# design.net
KiCad netlist of a schematic drawn in Altium Designer
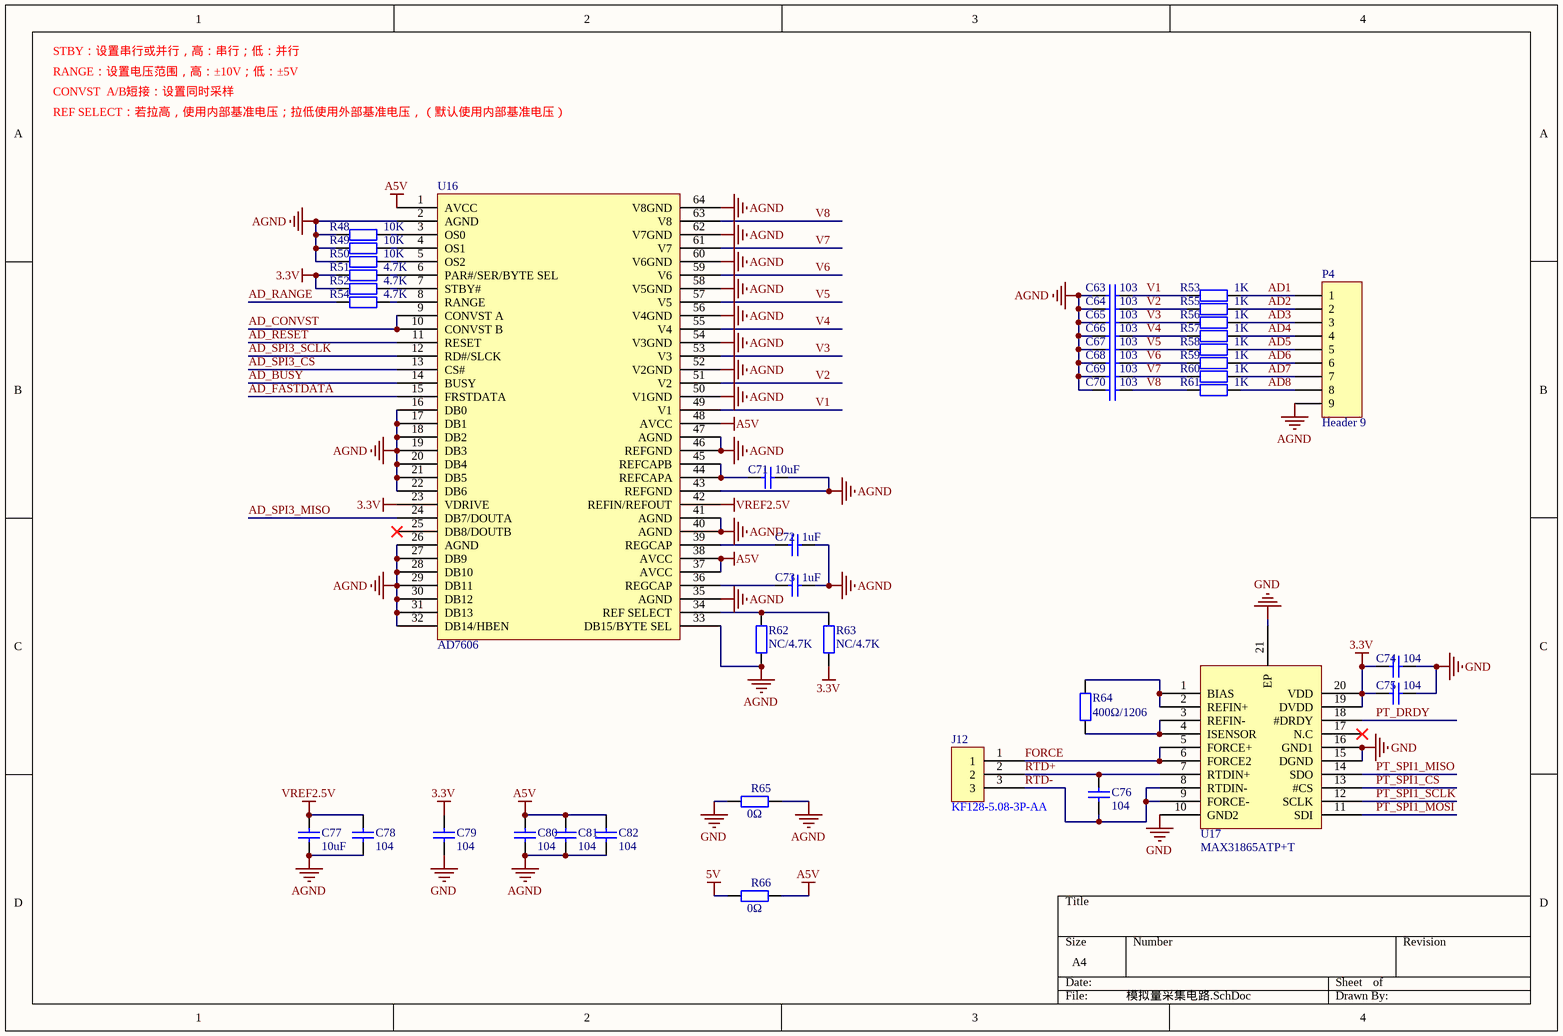
[diagram p0: 模拟量采集电路.SchDoc]

(export (version "E")
  (design (tool "Eeschema 10.0.6"))
  (components
    (comp (ref "C63")
      (value "103")
      (footprint "C 0603_L")
      (description "0603贴片电容")
      (fields (field (name "PUBLISHER") "Altium Limited"))
      (libsource (lib "STM32_PLC_20251215") (part "Cap"))
    )
    (comp (ref "C64")
      (value "103")
      (footprint "C 0603_L")
      (description "0603贴片电容")
      (fields (field (name "PUBLISHER") "Altium Limited"))
      (libsource (lib "STM32_PLC_20251215") (part "Cap"))
    )
    (comp (ref "C65")
      (value "103")
      (footprint "C 0603_L")
      (description "0603贴片电容")
      (fields (field (name "PUBLISHER") "Altium Limited"))
      (libsource (lib "STM32_PLC_20251215") (part "Cap"))
    )
    (comp (ref "C66")
      (value "103")
      (footprint "C 0603_L")
      (description "0603贴片电容")
      (fields (field (name "PUBLISHER") "Altium Limited"))
      (libsource (lib "STM32_PLC_20251215") (part "Cap"))
    )
    (comp (ref "C67")
      (value "103")
      (footprint "C 0603_L")
      (description "0603贴片电容")
      (fields (field (name "PUBLISHER") "Altium Limited"))
      (libsource (lib "STM32_PLC_20251215") (part "Cap"))
    )
    (comp (ref "C68")
      (value "103")
      (footprint "C 0603_L")
      (description "0603贴片电容")
      (fields (field (name "PUBLISHER") "Altium Limited"))
      (libsource (lib "STM32_PLC_20251215") (part "Cap"))
    )
    (comp (ref "C69")
      (value "103")
      (footprint "C 0603_L")
      (description "0603贴片电容")
      (fields (field (name "PUBLISHER") "Altium Limited"))
      (libsource (lib "STM32_PLC_20251215") (part "Cap"))
    )
    (comp (ref "C70")
      (value "103")
      (footprint "C 0603_L")
      (description "0603贴片电容")
      (fields (field (name "PUBLISHER") "Altium Limited"))
      (libsource (lib "STM32_PLC_20251215") (part "Cap"))
    )
    (comp (ref "C71")
      (value "10uF")
      (footprint "C 0603_L")
      (description "0603贴片电容")
      (fields (field (name "PUBLISHER") "Altium Limited"))
      (libsource (lib "STM32_PLC_20251215") (part "Cap"))
    )
    (comp (ref "C72")
      (value "1uF")
      (footprint "C 0603_L")
      (description "0603贴片电容")
      (fields (field (name "PUBLISHER") "Altium Limited"))
      (libsource (lib "STM32_PLC_20251215") (part "Cap"))
    )
    (comp (ref "C73")
      (value "1uF")
      (footprint "C 0603_L")
      (description "0603贴片电容")
      (fields (field (name "PUBLISHER") "Altium Limited"))
      (libsource (lib "STM32_PLC_20251215") (part "Cap"))
    )
    (comp (ref "C74")
      (value "104")
      (footprint "C 0603_L")
      (description "0603贴片电容")
      (fields (field (name "PUBLISHER") "Altium Limited"))
      (libsource (lib "STM32_PLC_20251215") (part "Cap"))
    )
    (comp (ref "C75")
      (value "104")
      (footprint "C 0603_L")
      (description "0603贴片电容")
      (fields (field (name "PUBLISHER") "Altium Limited"))
      (libsource (lib "STM32_PLC_20251215") (part "Cap"))
    )
    (comp (ref "C76")
      (value "104")
      (footprint "C 0603_L")
      (description "0603贴片电容")
      (fields (field (name "PUBLISHER") "Altium Limited"))
      (libsource (lib "STM32_PLC_20251215") (part "Cap"))
    )
    (comp (ref "C77")
      (value "10uF")
      (footprint "C 0603_L")
      (description "0603贴片电容")
      (fields (field (name "PUBLISHER") "Altium Limited"))
      (libsource (lib "STM32_PLC_20251215") (part "Cap"))
    )
    (comp (ref "C78")
      (value "104")
      (footprint "C 0603_L")
      (description "0603贴片电容")
      (fields (field (name "PUBLISHER") "Altium Limited"))
      (libsource (lib "STM32_PLC_20251215") (part "Cap"))
    )
    (comp (ref "C79")
      (value "104")
      (footprint "C 0603_L")
      (description "0603贴片电容")
      (fields (field (name "PUBLISHER") "Altium Limited"))
      (libsource (lib "STM32_PLC_20251215") (part "Cap"))
    )
    (comp (ref "C80")
      (value "104")
      (footprint "C 0603_L")
      (description "0603贴片电容")
      (fields (field (name "PUBLISHER") "Altium Limited"))
      (libsource (lib "STM32_PLC_20251215") (part "Cap"))
    )
    (comp (ref "C81")
      (value "104")
      (footprint "C 0603_L")
      (description "0603贴片电容")
      (fields (field (name "PUBLISHER") "Altium Limited"))
      (libsource (lib "STM32_PLC_20251215") (part "Cap"))
    )
    (comp (ref "C82")
      (value "104")
      (footprint "C 0603_L")
      (description "0603贴片电容")
      (fields (field (name "PUBLISHER") "Altium Limited"))
      (libsource (lib "STM32_PLC_20251215") (part "Cap"))
    )
    (comp (ref "J12")
      (value "KF128-5.08-3P-AA")
      (footprint "KF128-5.08-3P")
      (description "KF128-5.08-3P-AA端座")
      (fields (field (name "MANUFACTURER") "KEFA(科发)"))
      (libsource (lib "STM32_PLC_20251215") (part "KF128-5.08-3P-AA"))
    )
    (comp (ref "P4")
      (value "Header 9")
      (footprint "KF128-5.08-9P")
      (description "Header, 9-Pin")
      (fields (field (name "PUBLISHER") "Altium Limited"))
      (libsource (lib "Miscellaneous Connectors") (part "Header 9"))
    )
    (comp (ref "R48")
      (value "10K")
      (footprint "R 0603_L")
      (description "0603贴片电阻")
      (fields (field (name "版权归属") "源创客"))
      (libsource (lib "STM32_PLC_20251215") (part "Res"))
    )
    (comp (ref "R49")
      (value "10K")
      (footprint "R 0603_L")
      (description "0603贴片电阻")
      (fields (field (name "版权归属") "源创客"))
      (libsource (lib "STM32_PLC_20251215") (part "Res"))
    )
    (comp (ref "R50")
      (value "10K")
      (footprint "R 0603_L")
      (description "0603贴片电阻")
      (fields (field (name "版权归属") "源创客"))
      (libsource (lib "STM32_PLC_20251215") (part "Res"))
    )
    (comp (ref "R51")
      (value "4.7K")
      (footprint "R 0603_L")
      (description "0603贴片电阻")
      (fields (field (name "版权归属") "源创客"))
      (libsource (lib "STM32_PLC_20251215") (part "Res"))
    )
    (comp (ref "R52")
      (value "4.7K")
      (footprint "R 0603_L")
      (description "0603贴片电阻")
      (fields (field (name "版权归属") "源创客"))
      (libsource (lib "STM32_PLC_20251215") (part "Res"))
    )
    (comp (ref "R53")
      (value "1K")
      (footprint "R 0603_L")
      (description "0603贴片电阻")
      (fields (field (name "版权归属") "源创客"))
      (libsource (lib "STM32_PLC_20251215") (part "Res"))
    )
    (comp (ref "R54")
      (value "4.7K")
      (footprint "R 0603_L")
      (description "0603贴片电阻")
      (fields (field (name "版权归属") "源创客"))
      (libsource (lib "STM32_PLC_20251215") (part "Res"))
    )
    (comp (ref "R55")
      (value "1K")
      (footprint "R 0603_L")
      (description "0603贴片电阻")
      (fields (field (name "版权归属") "源创客"))
      (libsource (lib "STM32_PLC_20251215") (part "Res"))
    )
    (comp (ref "R56")
      (value "1K")
      (footprint "R 0603_L")
      (description "0603贴片电阻")
      (fields (field (name "版权归属") "源创客"))
      (libsource (lib "STM32_PLC_20251215") (part "Res"))
    )
    (comp (ref "R57")
      (value "1K")
      (footprint "R 0603_L")
      (description "0603贴片电阻")
      (fields (field (name "版权归属") "源创客"))
      (libsource (lib "STM32_PLC_20251215") (part "Res"))
    )
    (comp (ref "R58")
      (value "1K")
      (footprint "R 0603_L")
      (description "0603贴片电阻")
      (fields (field (name "版权归属") "源创客"))
      (libsource (lib "STM32_PLC_20251215") (part "Res"))
    )
    (comp (ref "R59")
      (value "1K")
      (footprint "R 0603_L")
      (description "0603贴片电阻")
      (fields (field (name "版权归属") "源创客"))
      (libsource (lib "STM32_PLC_20251215") (part "Res"))
    )
    (comp (ref "R60")
      (value "1K")
      (footprint "R 0603_L")
      (description "0603贴片电阻")
      (fields (field (name "版权归属") "源创客"))
      (libsource (lib "STM32_PLC_20251215") (part "Res"))
    )
    (comp (ref "R61")
      (value "1K")
      (footprint "R 0603_L")
      (description "0603贴片电阻")
      (fields (field (name "版权归属") "源创客"))
      (libsource (lib "STM32_PLC_20251215") (part "Res"))
    )
    (comp (ref "R62")
      (value "NC/4.7K")
      (footprint "R 0603_L")
      (description "0603贴片电阻")
      (fields (field (name "版权归属") "源创客"))
      (libsource (lib "STM32_PLC_20251215") (part "Res"))
    )
    (comp (ref "R63")
      (value "NC/4.7K")
      (footprint "R 0603_L")
      (description "0603贴片电阻")
      (fields (field (name "版权归属") "源创客"))
      (libsource (lib "STM32_PLC_20251215") (part "Res"))
    )
    (comp (ref "R64")
      (value "400Ω/1206")
      (footprint "R1206_L")
      (description "0603贴片电阻")
      (fields (field (name "版权归属") "源创客"))
      (libsource (lib "STM32_PLC_20251215") (part "Res"))
    )
    (comp (ref "R65")
      (value "0Ω")
      (footprint "R 0603_L")
      (description "0603贴片电阻")
      (fields (field (name "版权归属") "源创客"))
      (libsource (lib "STM32_PLC_20251215") (part "Res"))
    )
    (comp (ref "R66")
      (value "0Ω")
      (footprint "R 0603_L")
      (description "0603贴片电阻")
      (fields (field (name "版权归属") "源创客"))
      (libsource (lib "STM32_PLC_20251215") (part "Res"))
    )
    (comp (ref "U16")
      (value "AD7606")
      (footprint "LQFP64 10x10_M")
      (libsource (lib "STM32F407_PLC_20260104_") (part "AD7606"))
    )
    (comp (ref "U17")
      (value "MAX31865ATP+T")
      (footprint "QFN-20_L5.0-W5.0-P0.65-BL-EP")
      (fields (field (name "MANUFACTURER") "ADI(亚德诺)/MAXIM(美信)"))
      (libsource (lib "STM32F407_PLC_20260104_") (part "MAX31865ATP+T"))
    )
  )
  (nets
    (net (code "1") (name "/AD1") (class "Default")
      (node (ref "P4") (pin "1") (pinfunction "1_1") (pintype "passive"))
      (node (ref "R53") (pin "1") (pinfunction "1_1") (pintype "passive"))
    )
    (net (code "2") (name "/AD2") (class "Default")
      (node (ref "P4") (pin "2") (pinfunction "2_2") (pintype "passive"))
      (node (ref "R55") (pin "1") (pinfunction "1_1") (pintype "passive"))
    )
    (net (code "3") (name "/AD3") (class "Default")
      (node (ref "P4") (pin "3") (pinfunction "3_3") (pintype "passive"))
      (node (ref "R56") (pin "1") (pinfunction "1_1") (pintype "passive"))
    )
    (net (code "4") (name "/AD4") (class "Default")
      (node (ref "P4") (pin "4") (pinfunction "4_4") (pintype "passive"))
      (node (ref "R57") (pin "1") (pinfunction "1_1") (pintype "passive"))
    )
    (net (code "5") (name "/AD5") (class "Default")
      (node (ref "P4") (pin "5") (pinfunction "5_5") (pintype "passive"))
      (node (ref "R58") (pin "1") (pinfunction "1_1") (pintype "passive"))
    )
    (net (code "6") (name "/AD6") (class "Default")
      (node (ref "P4") (pin "6") (pinfunction "6_6") (pintype "passive"))
      (node (ref "R59") (pin "1") (pinfunction "1_1") (pintype "passive"))
    )
    (net (code "7") (name "/AD7") (class "Default")
      (node (ref "P4") (pin "7") (pinfunction "7_7") (pintype "passive"))
      (node (ref "R60") (pin "1") (pinfunction "1_1") (pintype "passive"))
    )
    (net (code "8") (name "/AD8") (class "Default")
      (node (ref "P4") (pin "8") (pinfunction "8_8") (pintype "passive"))
      (node (ref "R61") (pin "1") (pinfunction "1_1") (pintype "passive"))
    )
    (net (code "9") (name "/AD_BUSY") (class "Default")
      (node (ref "U16") (pin "14") (pinfunction "BUSY_14") (pintype "passive"))
    )
    (net (code "10") (name "/AD_CONVST") (class "Default")
      (node (ref "U16") (pin "10") (pinfunction "CONVST_B_10") (pintype "passive"))
      (node (ref "U16") (pin "9") (pinfunction "CONVST_A_9") (pintype "passive"))
    )
    (net (code "11") (name "/AD_FASTDATA") (class "Default")
      (node (ref "U16") (pin "15") (pinfunction "FRSTDATA_15") (pintype "passive"))
    )
    (net (code "12") (name "/AD_RANGE") (class "Default")
      (node (ref "R54") (pin "2") (pinfunction "2_2") (pintype "passive"))
    )
    (net (code "13") (name "/AD_RESET") (class "Default")
      (node (ref "U16") (pin "11") (pinfunction "RESET_11") (pintype "passive"))
    )
    (net (code "14") (name "/AD_SPI3_CS") (class "Default")
      (node (ref "U16") (pin "13") (pinfunction "CS#_13") (pintype "passive"))
    )
    (net (code "15") (name "/AD_SPI3_MISO") (class "Default")
      (node (ref "U16") (pin "24") (pinfunction "DB7/DOUTA_24") (pintype "passive"))
    )
    (net (code "16") (name "/AD_SPI3_SCLK") (class "Default")
      (node (ref "U16") (pin "12") (pinfunction "RD#/SLCK_12") (pintype "passive"))
    )
    (net (code "17") (name "/FORCE") (class "Default")
      (node (ref "J12") (pin "1") (pinfunction "1_1") (pintype "passive"))
      (node (ref "U17") (pin "5") (pinfunction "FORCE+_5") (pintype "passive"))
      (node (ref "U17") (pin "6") (pinfunction "FORCE2_6") (pintype "passive"))
    )
    (net (code "18") (name "/PT_DRDY") (class "Default")
      (node (ref "U17") (pin "18") (pinfunction "#DRDY_18") (pintype "passive"))
    )
    (net (code "19") (name "/PT_SPI1_CS") (class "Default")
      (node (ref "U17") (pin "13") (pinfunction "#CS_13") (pintype "passive"))
    )
    (net (code "20") (name "/PT_SPI1_MISO") (class "Default")
      (node (ref "U17") (pin "14") (pinfunction "SDO_14") (pintype "passive"))
    )
    (net (code "21") (name "/PT_SPI1_MOSI") (class "Default")
      (node (ref "U17") (pin "11") (pinfunction "SDI_11") (pintype "passive"))
    )
    (net (code "22") (name "/PT_SPI1_SCLK") (class "Default")
      (node (ref "U17") (pin "12") (pinfunction "SCLK_12") (pintype "passive"))
    )
    (net (code "23") (name "/RTD+") (class "Default")
      (node (ref "C76") (pin "2") (pinfunction "2_2") (pintype "passive"))
      (node (ref "J12") (pin "2") (pinfunction "2_2") (pintype "passive"))
      (node (ref "U17") (pin "7") (pinfunction "RTDIN+_7") (pintype "passive"))
    )
    (net (code "24") (name "/RTD-") (class "Default")
      (node (ref "C76") (pin "1") (pinfunction "1_1") (pintype "passive"))
      (node (ref "J12") (pin "3") (pinfunction "3_3") (pintype "passive"))
      (node (ref "U17") (pin "8") (pinfunction "RTDIN-_8") (pintype "passive"))
      (node (ref "U17") (pin "9") (pinfunction "FORCE-_9") (pintype "passive"))
    )
    (net (code "25") (name "/V1") (class "Default")
      (node (ref "C63") (pin "1") (pinfunction "1_1") (pintype "passive"))
      (node (ref "R53") (pin "2") (pinfunction "2_2") (pintype "passive"))
      (node (ref "U16") (pin "49") (pinfunction "V1_49") (pintype "passive"))
    )
    (net (code "26") (name "/V2") (class "Default")
      (node (ref "C64") (pin "1") (pinfunction "1_1") (pintype "passive"))
      (node (ref "R55") (pin "2") (pinfunction "2_2") (pintype "passive"))
      (node (ref "U16") (pin "51") (pinfunction "V2_51") (pintype "passive"))
    )
    (net (code "27") (name "/V3") (class "Default")
      (node (ref "C65") (pin "1") (pinfunction "1_1") (pintype "passive"))
      (node (ref "R56") (pin "2") (pinfunction "2_2") (pintype "passive"))
      (node (ref "U16") (pin "53") (pinfunction "V3_53") (pintype "passive"))
    )
    (net (code "28") (name "/V4") (class "Default")
      (node (ref "C66") (pin "1") (pinfunction "1_1") (pintype "passive"))
      (node (ref "R57") (pin "2") (pinfunction "2_2") (pintype "passive"))
      (node (ref "U16") (pin "55") (pinfunction "V4_55") (pintype "passive"))
    )
    (net (code "29") (name "/V5") (class "Default")
      (node (ref "C67") (pin "1") (pinfunction "1_1") (pintype "passive"))
      (node (ref "R58") (pin "2") (pinfunction "2_2") (pintype "passive"))
      (node (ref "U16") (pin "57") (pinfunction "V5_57") (pintype "passive"))
    )
    (net (code "30") (name "/V6") (class "Default")
      (node (ref "C68") (pin "1") (pinfunction "1_1") (pintype "passive"))
      (node (ref "R59") (pin "2") (pinfunction "2_2") (pintype "passive"))
      (node (ref "U16") (pin "59") (pinfunction "V6_59") (pintype "passive"))
    )
    (net (code "31") (name "/V7") (class "Default")
      (node (ref "C69") (pin "1") (pinfunction "1_1") (pintype "passive"))
      (node (ref "R60") (pin "2") (pinfunction "2_2") (pintype "passive"))
      (node (ref "U16") (pin "61") (pinfunction "V7_61") (pintype "passive"))
    )
    (net (code "32") (name "/V8") (class "Default")
      (node (ref "C70") (pin "1") (pinfunction "1_1") (pintype "passive"))
      (node (ref "R61") (pin "2") (pinfunction "2_2") (pintype "passive"))
      (node (ref "U16") (pin "63") (pinfunction "V8_63") (pintype "passive"))
    )
    (net (code "33") (name "3.3V") (class "Default")
      (node (ref "C74") (pin "2") (pinfunction "2_2") (pintype "passive"))
      (node (ref "C75") (pin "2") (pinfunction "2_2") (pintype "passive"))
      (node (ref "C79") (pin "2") (pinfunction "2_2") (pintype "passive"))
      (node (ref "R51") (pin "2") (pinfunction "2_2") (pintype "passive"))
      (node (ref "R52") (pin "2") (pinfunction "2_2") (pintype "passive"))
      (node (ref "R63") (pin "2") (pinfunction "2_2") (pintype "passive"))
      (node (ref "U16") (pin "23") (pinfunction "VDRIVE_23") (pintype "passive"))
      (node (ref "U17") (pin "19") (pinfunction "DVDD_19") (pintype "passive"))
      (node (ref "U17") (pin "20") (pinfunction "VDD_20") (pintype "passive"))
    )
    (net (code "34") (name "5V") (class "Default")
      (node (ref "R66") (pin "1") (pinfunction "1_1") (pintype "passive"))
    )
    (net (code "35") (name "A5V") (class "Default")
      (node (ref "C80") (pin "2") (pinfunction "2_2") (pintype "passive"))
      (node (ref "C81") (pin "2") (pinfunction "2_2") (pintype "passive"))
      (node (ref "C82") (pin "2") (pinfunction "2_2") (pintype "passive"))
      (node (ref "R66") (pin "2") (pinfunction "2_2") (pintype "passive"))
      (node (ref "U16") (pin "1") (pinfunction "AVCC_1") (pintype "passive"))
      (node (ref "U16") (pin "37") (pinfunction "AVCC_37") (pintype "passive"))
      (node (ref "U16") (pin "38") (pinfunction "AVCC_38") (pintype "passive"))
      (node (ref "U16") (pin "48") (pinfunction "AVCC_48") (pintype "passive"))
    )
    (net (code "36") (name "AGND") (class "Default")
      (node (ref "C63") (pin "2") (pinfunction "2_2") (pintype "passive"))
      (node (ref "C64") (pin "2") (pinfunction "2_2") (pintype "passive"))
      (node (ref "C65") (pin "2") (pinfunction "2_2") (pintype "passive"))
      (node (ref "C66") (pin "2") (pinfunction "2_2") (pintype "passive"))
      (node (ref "C67") (pin "2") (pinfunction "2_2") (pintype "passive"))
      (node (ref "C68") (pin "2") (pinfunction "2_2") (pintype "passive"))
      (node (ref "C69") (pin "2") (pinfunction "2_2") (pintype "passive"))
      (node (ref "C70") (pin "2") (pinfunction "2_2") (pintype "passive"))
      (node (ref "C71") (pin "1") (pinfunction "1_1") (pintype "passive"))
      (node (ref "C72") (pin "1") (pinfunction "1_1") (pintype "passive"))
      (node (ref "C73") (pin "1") (pinfunction "1_1") (pintype "passive"))
      (node (ref "C77") (pin "2") (pinfunction "2_2") (pintype "passive"))
      (node (ref "C78") (pin "1") (pinfunction "1_1") (pintype "passive"))
      (node (ref "C80") (pin "1") (pinfunction "1_1") (pintype "passive"))
      (node (ref "C81") (pin "1") (pinfunction "1_1") (pintype "passive"))
      (node (ref "C82") (pin "1") (pinfunction "1_1") (pintype "passive"))
      (node (ref "P4") (pin "9") (pinfunction "9_9") (pintype "passive"))
      (node (ref "R48") (pin "2") (pinfunction "2_2") (pintype "passive"))
      (node (ref "R49") (pin "2") (pinfunction "2_2") (pintype "passive"))
      (node (ref "R50") (pin "2") (pinfunction "2_2") (pintype "passive"))
      (node (ref "R62") (pin "2") (pinfunction "2_2") (pintype "passive"))
      (node (ref "R65") (pin "2") (pinfunction "2_2") (pintype "passive"))
      (node (ref "U16") (pin "16") (pinfunction "DB0_16") (pintype "passive"))
      (node (ref "U16") (pin "17") (pinfunction "DB1_17") (pintype "passive"))
      (node (ref "U16") (pin "18") (pinfunction "DB2_18") (pintype "passive"))
      (node (ref "U16") (pin "19") (pinfunction "DB3_19") (pintype "passive"))
      (node (ref "U16") (pin "2") (pinfunction "AGND_2") (pintype "passive"))
      (node (ref "U16") (pin "20") (pinfunction "DB4_20") (pintype "passive"))
      (node (ref "U16") (pin "21") (pinfunction "DB5_21") (pintype "passive"))
      (node (ref "U16") (pin "22") (pinfunction "DB6_22") (pintype "passive"))
      (node (ref "U16") (pin "26") (pinfunction "AGND_26") (pintype "passive"))
      (node (ref "U16") (pin "27") (pinfunction "DB9_27") (pintype "passive"))
      (node (ref "U16") (pin "28") (pinfunction "DB10_28") (pintype "passive"))
      (node (ref "U16") (pin "29") (pinfunction "DB11_29") (pintype "passive"))
      (node (ref "U16") (pin "30") (pinfunction "DB12_30") (pintype "passive"))
      (node (ref "U16") (pin "31") (pinfunction "DB13_31") (pintype "passive"))
      (node (ref "U16") (pin "32") (pinfunction "DB14/HBEN_32") (pintype "passive"))
      (node (ref "U16") (pin "33") (pinfunction "DB15/BYTE_SEL_33") (pintype "passive"))
      (node (ref "U16") (pin "35") (pinfunction "AGND_35") (pintype "passive"))
      (node (ref "U16") (pin "40") (pinfunction "AGND_40") (pintype "passive"))
      (node (ref "U16") (pin "41") (pinfunction "AGND_41") (pintype "passive"))
      (node (ref "U16") (pin "43") (pinfunction "REFGND_43") (pintype "passive"))
      (node (ref "U16") (pin "46") (pinfunction "REFGND_46") (pintype "passive"))
      (node (ref "U16") (pin "47") (pinfunction "AGND_47") (pintype "passive"))
      (node (ref "U16") (pin "50") (pinfunction "V1GND_50") (pintype "passive"))
      (node (ref "U16") (pin "52") (pinfunction "V2GND_52") (pintype "passive"))
      (node (ref "U16") (pin "54") (pinfunction "V3GND_54") (pintype "passive"))
      (node (ref "U16") (pin "56") (pinfunction "V4GND_56") (pintype "passive"))
      (node (ref "U16") (pin "58") (pinfunction "V5GND_58") (pintype "passive"))
      (node (ref "U16") (pin "60") (pinfunction "V6GND_60") (pintype "passive"))
      (node (ref "U16") (pin "62") (pinfunction "V7GND_62") (pintype "passive"))
      (node (ref "U16") (pin "64") (pinfunction "V8GND_64") (pintype "passive"))
    )
    (net (code "37") (name "GND") (class "Default")
      (node (ref "C74") (pin "1") (pinfunction "1_1") (pintype "passive"))
      (node (ref "C75") (pin "1") (pinfunction "1_1") (pintype "passive"))
      (node (ref "C79") (pin "1") (pinfunction "1_1") (pintype "passive"))
      (node (ref "R65") (pin "1") (pinfunction "1_1") (pintype "passive"))
      (node (ref "U17") (pin "10") (pinfunction "GND2_10") (pintype "passive"))
      (node (ref "U17") (pin "15") (pinfunction "DGND_15") (pintype "passive"))
      (node (ref "U17") (pin "16") (pinfunction "GND1_16") (pintype "passive"))
      (node (ref "U17") (pin "21") (pinfunction "EP_21") (pintype "passive"))
    )
    (net (code "38") (name "Net-(C72-Pad2)") (class "Default")
      (node (ref "C72") (pin "2") (pinfunction "2_2") (pintype "passive"))
      (node (ref "U16") (pin "39") (pinfunction "REGCAP_39") (pintype "passive"))
    )
    (net (code "39") (name "Net-(C73-Pad2)") (class "Default")
      (node (ref "C73") (pin "2") (pinfunction "2_2") (pintype "passive"))
      (node (ref "U16") (pin "36") (pinfunction "REGCAP_36") (pintype "passive"))
    )
    (net (code "40") (name "Net-(U16-OS0)") (class "Default")
      (node (ref "R48") (pin "1") (pinfunction "1_1") (pintype "passive"))
      (node (ref "U16") (pin "3") (pinfunction "OS0_3") (pintype "passive"))
    )
    (net (code "41") (name "Net-(U16-OS1)") (class "Default")
      (node (ref "R49") (pin "1") (pinfunction "1_1") (pintype "passive"))
      (node (ref "U16") (pin "4") (pinfunction "OS1_4") (pintype "passive"))
    )
    (net (code "42") (name "Net-(U16-OS2)") (class "Default")
      (node (ref "R50") (pin "1") (pinfunction "1_1") (pintype "passive"))
      (node (ref "U16") (pin "5") (pinfunction "OS2_5") (pintype "passive"))
    )
    (net (code "43") (name "Net-(U16-PAR#{slash}SER{slash}BYTE_SEL)") (class "Default")
      (node (ref "R51") (pin "1") (pinfunction "1_1") (pintype "passive"))
      (node (ref "U16") (pin "6") (pinfunction "PAR#/SER/BYTE_SEL_6") (pintype "passive"))
    )
    (net (code "44") (name "Net-(U16-RANGE)") (class "Default")
      (node (ref "R54") (pin "1") (pinfunction "1_1") (pintype "passive"))
      (node (ref "U16") (pin "8") (pinfunction "RANGE_8") (pintype "passive"))
    )
    (net (code "45") (name "Net-(U16-REFCAPA)") (class "Default")
      (node (ref "C71") (pin "2") (pinfunction "2_2") (pintype "passive"))
      (node (ref "U16") (pin "44") (pinfunction "REFCAPA_44") (pintype "passive"))
      (node (ref "U16") (pin "45") (pinfunction "REFCAPB_45") (pintype "passive"))
    )
    (net (code "46") (name "Net-(U16-REF_SELECT)") (class "Default")
      (node (ref "R62") (pin "1") (pinfunction "1_1") (pintype "passive"))
      (node (ref "R63") (pin "1") (pinfunction "1_1") (pintype "passive"))
      (node (ref "U16") (pin "34") (pinfunction "REF_SELECT_34") (pintype "passive"))
    )
    (net (code "47") (name "Net-(U16-STBY#)") (class "Default")
      (node (ref "R52") (pin "1") (pinfunction "1_1") (pintype "passive"))
      (node (ref "U16") (pin "7") (pinfunction "STBY#_7") (pintype "passive"))
    )
    (net (code "48") (name "Net-(U17-BIAS)") (class "Default")
      (node (ref "R64") (pin "1") (pinfunction "1_1") (pintype "passive"))
      (node (ref "U17") (pin "1") (pinfunction "BIAS_1") (pintype "passive"))
      (node (ref "U17") (pin "2") (pinfunction "REFIN+_2") (pintype "passive"))
    )
    (net (code "49") (name "Net-(U17-ISENSOR)") (class "Default")
      (node (ref "R64") (pin "2") (pinfunction "2_2") (pintype "passive"))
      (node (ref "U17") (pin "3") (pinfunction "REFIN-_3") (pintype "passive"))
      (node (ref "U17") (pin "4") (pinfunction "ISENSOR_4") (pintype "passive"))
    )
    (net (code "50") (name "VREF2.5V") (class "Default")
      (node (ref "C77") (pin "1") (pinfunction "1_1") (pintype "passive"))
      (node (ref "C78") (pin "2") (pinfunction "2_2") (pintype "passive"))
      (node (ref "U16") (pin "42") (pinfunction "REFIN/REFOUT_42") (pintype "passive"))
    )
    (net (code "51") (name "unconnected-(U16-DB8{slash}DOUTB-Pad25)") (class "Default")
      (node (ref "U16") (pin "25") (pinfunction "DB8/DOUTB_25") (pintype "passive+no_connect"))
    )
    (net (code "52") (name "unconnected-(U17-N.C-Pad17)") (class "Default")
      (node (ref "U17") (pin "17") (pinfunction "N.C_17") (pintype "passive+no_connect"))
    )
  )
)
